# SaV64_v133_oops.net
KiCad netlist of a schematic drawn in EAGLE
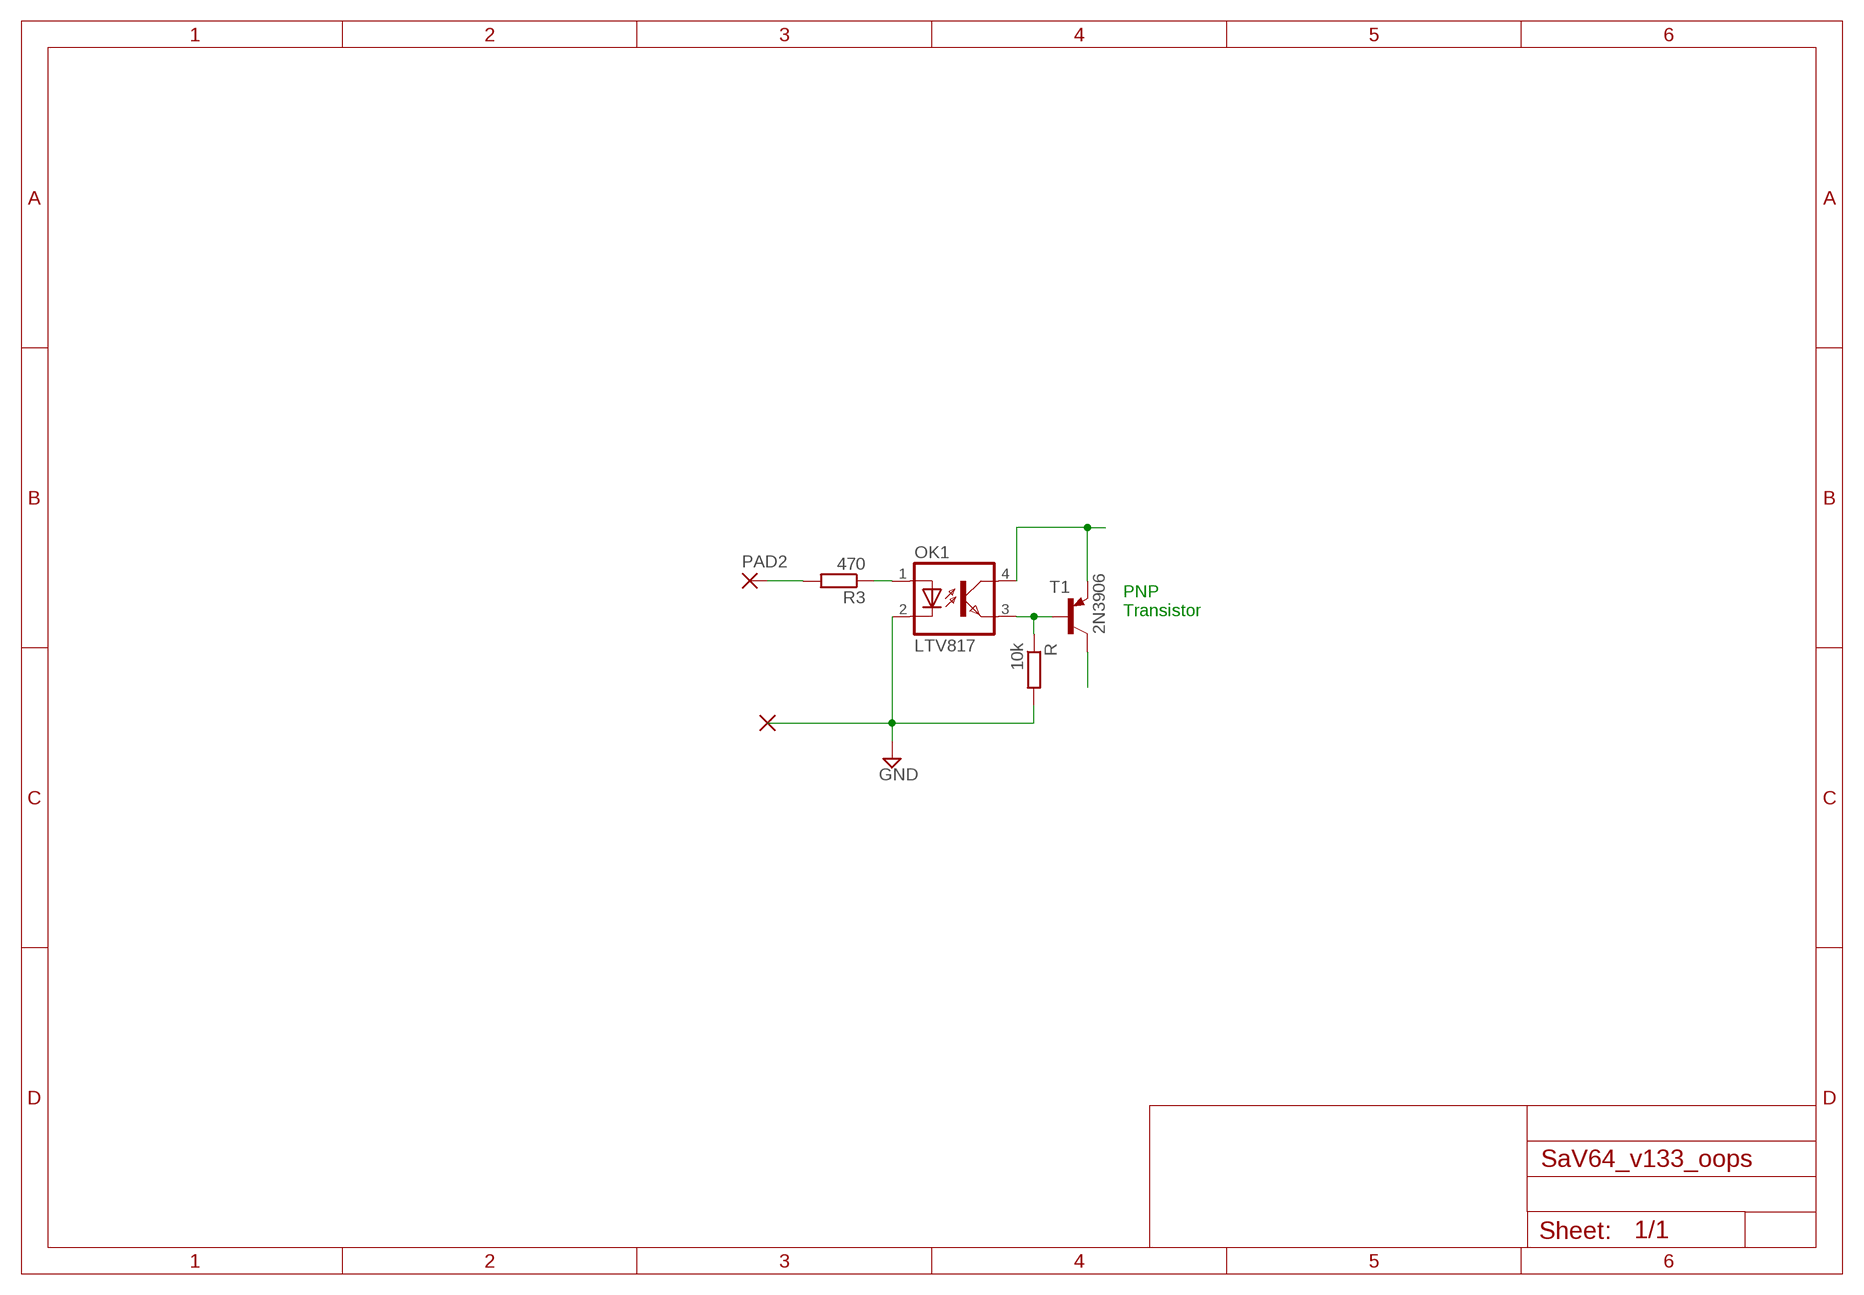
[diagram p0: schematic, sheet 1]

(export (version "E")
  (design (tool "Eeschema 10.0.6"))
  (components
    (comp (ref "OK1")
      (value "LTV817")
      (footprint "eagle-import:SMD4")
      (libsource (lib "eagle-import") (part "LTV816S"))
    )
    (comp (ref "PAD2")
      (value "1,6/0,8")
      (footprint "eagle-import:1,6_0,8")
      (libsource (lib "eagle-import") (part "1,6/0,8"))
    )
    (comp (ref "R")
      (value "10k")
      (footprint "eagle-import:R1210W")
      (libsource (lib "eagle-import") (part "R-EU_R1210W"))
    )
    (comp (ref "R3")
      (value "470")
      (footprint "eagle-import:R1210W")
      (libsource (lib "eagle-import") (part "R-EU_R1210W"))
    )
    (comp (ref "T1")
      (value "2N3906")
      (footprint "eagle-import:TO92")
      (libsource (lib "eagle-import") (part "2N3906"))
    )
  )
  (nets
    (net (code "1") (name "GND") (class "Default")
      (node (ref "OK1") (pin "2") (pinfunction "C_2") (pintype "passive"))
      (node (ref "R") (pin "2") (pinfunction "2_2") (pintype "passive"))
    )
    (net (code "2") (name "Net-(OK1-A)") (class "Default")
      (node (ref "OK1") (pin "1") (pinfunction "A_1") (pintype "passive"))
      (node (ref "R3") (pin "1") (pinfunction "1_1") (pintype "passive"))
    )
    (net (code "3") (name "Net-(OK1-COL)") (class "Default")
      (node (ref "OK1") (pin "4") (pinfunction "COL_4") (pintype "passive"))
      (node (ref "T1") (pin "3") (pinfunction "E_3") (pintype "passive"))
    )
    (net (code "4") (name "Net-(OK1-EMIT)") (class "Default")
      (node (ref "OK1") (pin "3") (pinfunction "EMIT_3") (pintype "passive"))
      (node (ref "R") (pin "1") (pinfunction "1_1") (pintype "passive"))
      (node (ref "T1") (pin "2") (pinfunction "B_2") (pintype "passive"))
    )
    (net (code "5") (name "Net-(PAD2-P)") (class "Default")
      (node (ref "PAD2") (pin "1") (pinfunction "P_1") (pintype "passive"))
      (node (ref "R3") (pin "2") (pinfunction "2_2") (pintype "passive"))
    )
    (net (code "6") (name "unconnected-(T1-C-Pad1)") (class "Default")
      (node (ref "T1") (pin "1") (pinfunction "C_1") (pintype "passive"))
    )
  )
)
